# CH9374.net
KiCad netlist of a schematic drawn in Altium Designer
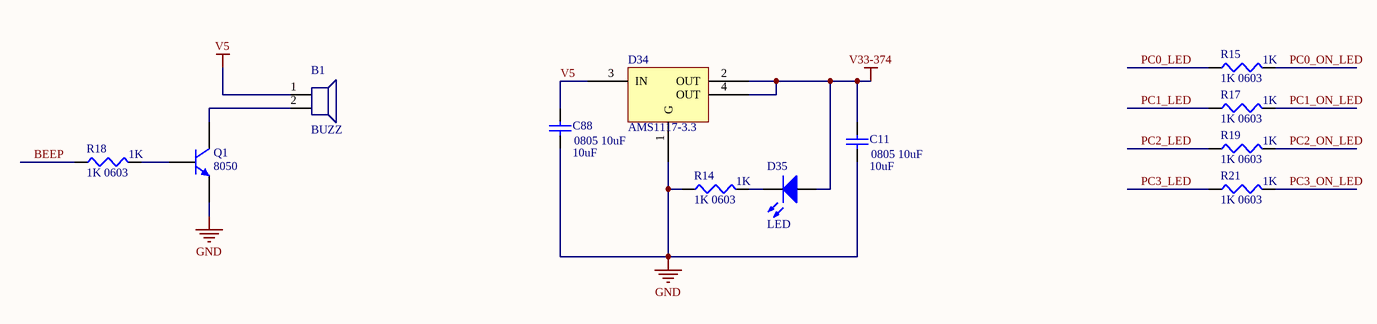
[diagram p0: CH9374.SchDoc]

(export (version "E")
  (design (tool "Eeschema 10.0.6"))
  (components
    (comp (ref "B1") (value "BUZZ") (footprint "BUZZ") (libsource (lib "Common Device") (part "BUZZ")))
    (comp (ref "C11")
      (value "0805 10uF")
      (footprint "C0805")
      (description "Capacitor (Semiconductor SIM Model)")
      (fields (field (name "ALTIUM_VALUE") "10uF") (field (name "PUBLISHER") "Altium Limited"))
      (libsource (lib "Miscellaneous Devices") (part "Cap Semi"))
    )
    (comp (ref "C88")
      (value "0805 10uF")
      (footprint "C0805")
      (description "Capacitor (Semiconductor SIM Model)")
      (fields (field (name "ALTIUM_VALUE") "10uF") (field (name "PUBLISHER") "Altium Limited"))
      (libsource (lib "Miscellaneous Devices") (part "Cap Semi"))
    )
    (comp (ref "D34")
      (value "AMS1117-3.3")
      (footprint "SOT-223")
      (libsource (lib "MyLib") (part "AMS1117-3.3"))
    )
    (comp (ref "D35") (value "LED") (footprint "LED0603") (libsource (lib "Common Device") (part "LED")))
    (comp (ref "Q1")
      (value "8050")
      (footprint "TO-226-AA")
      (description "NPN Bipolar Transistor")
      (fields (field (name "PUBLISHER") "Altium Limited"))
      (libsource (lib "Miscellaneous Devices") (part "NPN"))
    )
    (comp (ref "R14")
      (value "1K 0603")
      (footprint "R0603")
      (description "Resistor")
      (fields (field (name "ALTIUM_VALUE") "1K") (field (name "PUBLISHER") "Altium Limited"))
      (libsource (lib "Miscellaneous Devices") (part "Res3"))
    )
    (comp (ref "R15")
      (value "1K 0603")
      (footprint "R0603")
      (description "Resistor")
      (fields (field (name "ALTIUM_VALUE") "1K") (field (name "PUBLISHER") "Altium Limited"))
      (libsource (lib "Miscellaneous Devices") (part "Res3"))
    )
    (comp (ref "R17")
      (value "1K 0603")
      (footprint "R0603")
      (description "Resistor")
      (fields (field (name "ALTIUM_VALUE") "1K") (field (name "PUBLISHER") "Altium Limited"))
      (libsource (lib "Miscellaneous Devices") (part "Res3"))
    )
    (comp (ref "R18")
      (value "1K 0603")
      (footprint "R0603")
      (description "Resistor")
      (fields (field (name "ALTIUM_VALUE") "1K") (field (name "PUBLISHER") "Altium Limited"))
      (libsource (lib "Miscellaneous Devices") (part "Res3"))
    )
    (comp (ref "R19")
      (value "1K 0603")
      (footprint "R0603")
      (description "Resistor")
      (fields (field (name "ALTIUM_VALUE") "1K") (field (name "PUBLISHER") "Altium Limited"))
      (libsource (lib "Miscellaneous Devices") (part "Res3"))
    )
    (comp (ref "R21")
      (value "1K 0603")
      (footprint "R0603")
      (description "Resistor")
      (fields (field (name "ALTIUM_VALUE") "1K") (field (name "PUBLISHER") "Altium Limited"))
      (libsource (lib "Miscellaneous Devices") (part "Res3"))
    )
  )
  (nets
    (net (code "1") (name "/BEEP") (class "Default")
      (node (ref "R18") (pin "1") (pinfunction "1_1") (pintype "passive"))
    )
    (net (code "2") (name "/PC0_LED") (class "Default")
      (node (ref "R15") (pin "1") (pinfunction "1_1") (pintype "passive"))
    )
    (net (code "3") (name "/PC0_ON_LED") (class "Default")
      (node (ref "R15") (pin "2") (pinfunction "2_2") (pintype "passive"))
    )
    (net (code "4") (name "/PC1_LED") (class "Default")
      (node (ref "R17") (pin "1") (pinfunction "1_1") (pintype "passive"))
    )
    (net (code "5") (name "/PC1_ON_LED") (class "Default")
      (node (ref "R17") (pin "2") (pinfunction "2_2") (pintype "passive"))
    )
    (net (code "6") (name "/PC2_LED") (class "Default")
      (node (ref "R19") (pin "1") (pinfunction "1_1") (pintype "passive"))
    )
    (net (code "7") (name "/PC2_ON_LED") (class "Default")
      (node (ref "R19") (pin "2") (pinfunction "2_2") (pintype "passive"))
    )
    (net (code "8") (name "/PC3_LED") (class "Default")
      (node (ref "R21") (pin "1") (pinfunction "1_1") (pintype "passive"))
    )
    (net (code "9") (name "/PC3_ON_LED") (class "Default")
      (node (ref "R21") (pin "2") (pinfunction "2_2") (pintype "passive"))
    )
    (net (code "10") (name "GND") (class "Default")
      (node (ref "C11") (pin "1") (pinfunction "1_1") (pintype "passive"))
      (node (ref "C88") (pin "1") (pinfunction "1_1") (pintype "passive"))
      (node (ref "D34") (pin "1") (pinfunction "G_1") (pintype "passive"))
      (node (ref "Q1") (pin "3") (pinfunction "E_3") (pintype "passive"))
      (node (ref "R14") (pin "1") (pinfunction "1_1") (pintype "passive"))
    )
    (net (code "11") (name "Net-(B1-GND)") (class "Default")
      (node (ref "B1") (pin "2") (pinfunction "GND_2") (pintype "passive"))
      (node (ref "Q1") (pin "1") (pinfunction "C_1") (pintype "passive"))
    )
    (net (code "12") (name "Net-(D35-K)") (class "Default")
      (node (ref "D35") (pin "2") (pinfunction "K_2") (pintype "passive"))
      (node (ref "R14") (pin "2") (pinfunction "2_2") (pintype "passive"))
    )
    (net (code "13") (name "Net-(Q1-B)") (class "Default")
      (node (ref "Q1") (pin "2") (pinfunction "B_2") (pintype "passive"))
      (node (ref "R18") (pin "2") (pinfunction "2_2") (pintype "passive"))
    )
    (net (code "14") (name "V5") (class "Default")
      (node (ref "B1") (pin "1") (pinfunction "VCC_1") (pintype "passive"))
      (node (ref "C88") (pin "2") (pinfunction "2_2") (pintype "passive"))
      (node (ref "D34") (pin "3") (pinfunction "IN_3") (pintype "passive"))
    )
    (net (code "15") (name "V33-374") (class "Default")
      (node (ref "C11") (pin "2") (pinfunction "2_2") (pintype "passive"))
      (node (ref "D34") (pin "2") (pinfunction "OUT_2") (pintype "passive"))
      (node (ref "D34") (pin "4") (pinfunction "OUT_4") (pintype "passive"))
      (node (ref "D35") (pin "1") (pinfunction "A_1") (pintype "passive"))
    )
  )
)
